# SCH_Geiger.net
KiCad netlist of a schematic drawn in EasyEDA
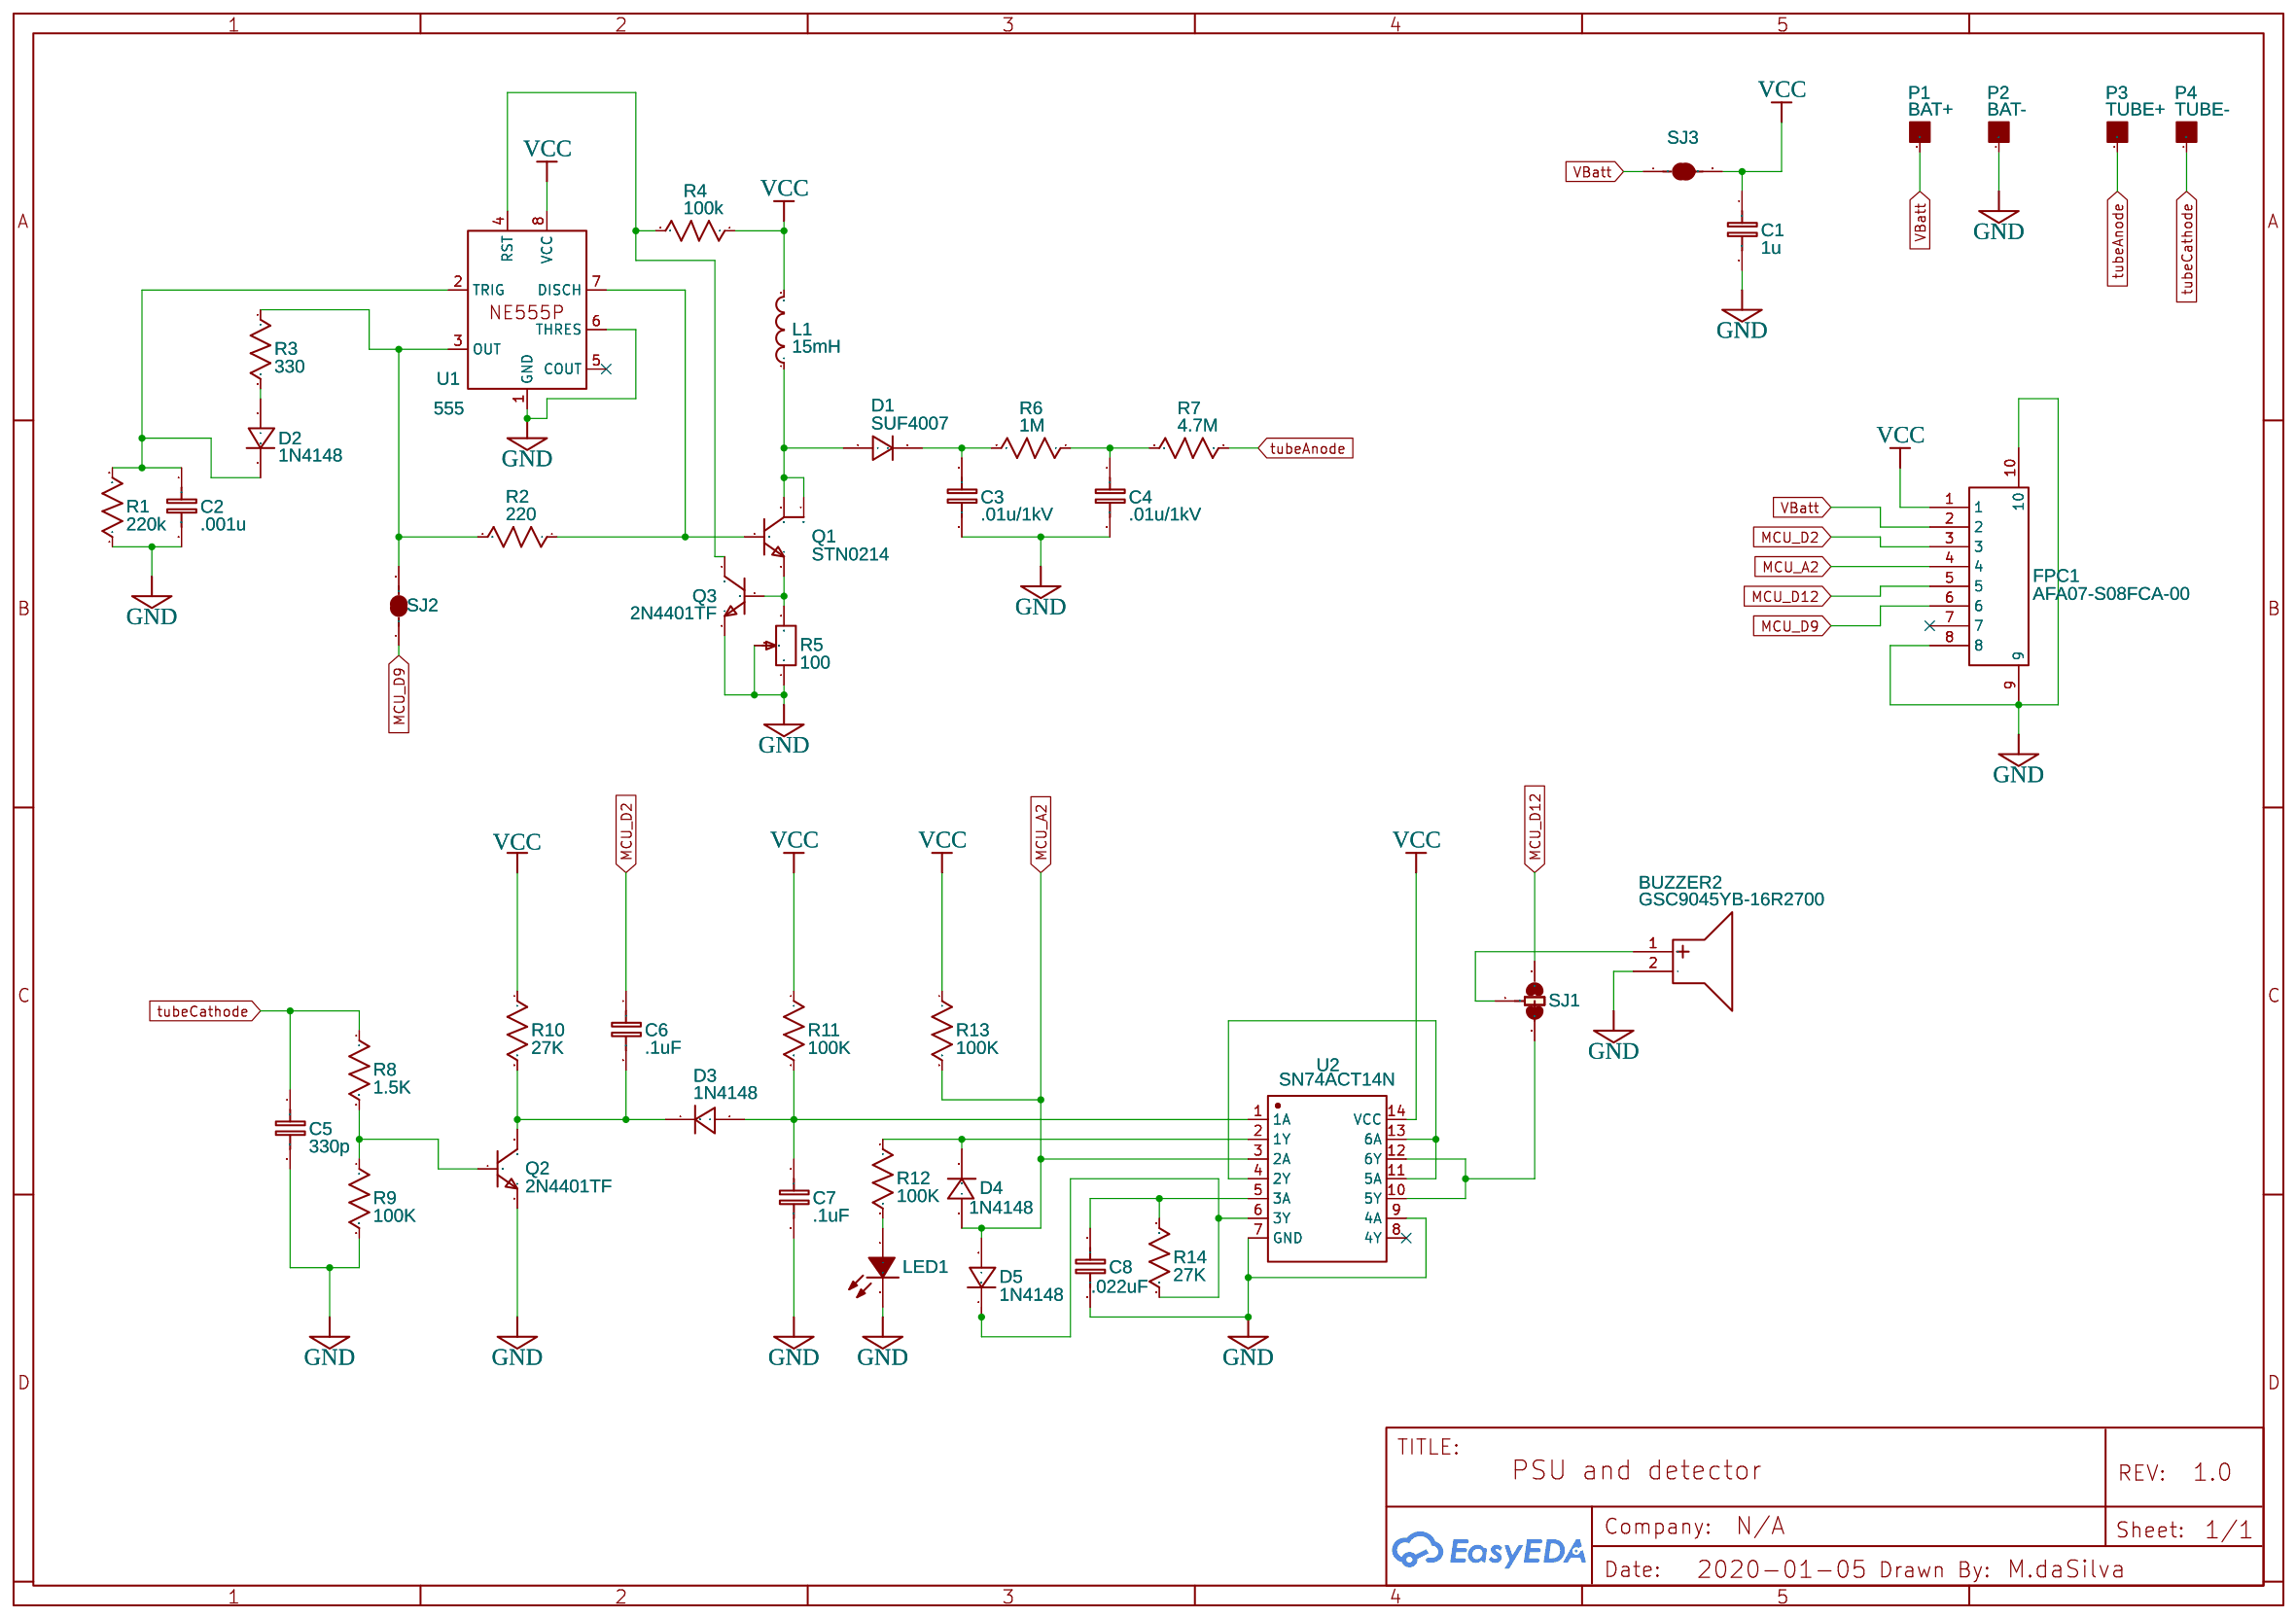
[diagram p0: schematic sheet]

(export (version "E")
  (design (tool "Eeschema 10.0.6"))
  (components
    (comp (ref "BUZZER2")
      (value "GSC9045YB-16R2700")
      (fields (field (name "BOM_Supplier Part") "C255324"))
      (libsource (lib "") (part "GSC9045YB-16R2700"))
    )
    (comp (ref "C1")
      (value "1u")
      (fields (field (name "BOM_Manufacturer Part") "0805B105K500AT"))
      (libsource (lib "") (part "Cap_RAD-0.1_EU_1"))
    )
    (comp (ref "C2")
      (value ".001u")
      (fields (field (name "BOM_Manufacturer Part") "0805B102J500NT"))
      (libsource (lib "") (part "Cap_RAD-0.1_EU_1"))
    )
    (comp (ref "C3")
      (value ".01u/1kV")
      (fields
        (field (name "BOM_Manufacturer Part") "1210B103K102NT")
        (field (name "BOM_Supplier Part") "C225089")
      )
      (libsource (lib "") (part "Cap_RAD-0.1_EU_2"))
    )
    (comp (ref "C4")
      (value ".01u/1kV")
      (fields
        (field (name "BOM_Manufacturer Part") "1210B103K102NT")
        (field (name "BOM_Supplier Part") "C225089")
      )
      (libsource (lib "") (part "Cap_RAD-0.1_EU_1"))
    )
    (comp (ref "C5")
      (value "330p")
      (fields (field (name "BOM_Manufacturer Part") "0805B331K101NT"))
      (libsource (lib "") (part "Cap_RAD-0.1_EU_3"))
    )
    (comp (ref "C6")
      (value ".1uF")
      (fields (field (name "BOM_Manufacturer Part") "0805B102J500NT"))
      (libsource (lib "") (part "Cap_RAD-0.1_EU"))
    )
    (comp (ref "C7")
      (value ".1uF")
      (fields (field (name "BOM_Manufacturer Part") "0805B104J500NT"))
      (libsource (lib "") (part "Cap_RAD-0.1_EU"))
    )
    (comp (ref "C8")
      (value ".022uF")
      (fields (field (name "BOM_Manufacturer Part") "CC0805KRX7R9BB223"))
      (libsource (lib "") (part "Cap_RAD-0.1_EU_3"))
    )
    (comp (ref "D1")
      (value "SUF4007")
      (fields (field (name "BOM_Supplier Part") "C212757"))
      (libsource (lib "") (part "SUF4007"))
    )
    (comp (ref "D2")
      (value "1N4148")
      (fields (field (name "BOM_Manufacturer Part") "1N4148W") (field (name "BOM_Supplier Part") "C402213"))
      (libsource (lib "") (part "1N4148W_C402213_1"))
    )
    (comp (ref "D3")
      (value "1N4148")
      (fields (field (name "BOM_Manufacturer Part") "1N4148W") (field (name "BOM_Supplier Part") "C402213"))
      (libsource (lib "") (part "1N4148W_C402213_2"))
    )
    (comp (ref "D4")
      (value "1N4148")
      (fields (field (name "BOM_Manufacturer Part") "1N4148W") (field (name "BOM_Supplier Part") "C402213"))
      (libsource (lib "") (part "1N4148W_C402213"))
    )
    (comp (ref "D5")
      (value "1N4148")
      (fields (field (name "BOM_Manufacturer Part") "1N4148W") (field (name "BOM_Supplier Part") "C402213"))
      (libsource (lib "") (part "1N4148W_C402213_1"))
    )
    (comp (ref "FPC1")
      (value "AFA07-S08FCA-00")
      (fields (field (name "BOM_Supplier Part") "C262714"))
      (libsource (lib "") (part "AFA07-S08FCA-00"))
    )
    (comp (ref "L1")
      (value "15mH")
      (fields
        (field (name "BOM_Manufacturer Part") "FNR6045S153KT")
        (field (name "BOM_Supplier Part") "C168110")
      )
      (libsource (lib "") (part "FNR6045S153KT"))
    )
    (comp (ref "LED1")
      (value "17-215/T7D-JU1V1E/3T")
      (fields (field (name "BOM_Supplier Part") "C264428"))
      (libsource (lib "") (part "17-215/T7D-JU1V1E/3T"))
    )
    (comp (ref "P1") (value "BAT+") (libsource (lib "") (part "3MMPAD")))
    (comp (ref "P2") (value "BAT-") (libsource (lib "") (part "3MMPAD")))
    (comp (ref "P3") (value "TUBE+") (libsource (lib "") (part "3MMPAD")))
    (comp (ref "P4") (value "TUBE-") (libsource (lib "") (part "3MMPAD")))
    (comp (ref "Q1") (value "STN0214") (libsource (lib "") (part "STN851")))
    (comp (ref "Q2")
      (value "2N4401TF")
      (fields (field (name "BOM_Supplier Part") "C83940"))
      (libsource (lib "") (part "2N4401TF"))
    )
    (comp (ref "Q3")
      (value "2N4401TF")
      (fields (field (name "BOM_Supplier Part") "C83940"))
      (libsource (lib "") (part "2N4401TF_1"))
    )
    (comp (ref "R1")
      (value "220k")
      (fields (field (name "BOM_Manufacturer Part") "RTT052203FTP"))
      (libsource (lib "") (part "Res_AXIAL-0.3(1/8W)_US_2"))
    )
    (comp (ref "R2")
      (value "220")
      (fields (field (name "BOM_Manufacturer Part") "RTT052200FTP"))
      (libsource (lib "") (part "Res_AXIAL-0.3(1/8W)_US_1"))
    )
    (comp (ref "R3")
      (value "330")
      (fields (field (name "BOM_Manufacturer Part") "RTT053300FTP"))
      (libsource (lib "") (part "Res_AXIAL-0.3(1/8W)_US"))
    )
    (comp (ref "R4")
      (value "100k")
      (fields (field (name "BOM_Manufacturer Part") "RTT051003FTP"))
      (libsource (lib "") (part "Res_AXIAL-0.3(1/8W)_US_1"))
    )
    (comp (ref "R5")
      (value "100")
      (fields
        (field (name "BOM_Manufacturer Part") "VG039NCHXTB101")
        (field (name "BOM_Supplier Part") "C128542")
      )
      (libsource (lib "") (part "VG039NCHXTB101"))
    )
    (comp (ref "R6")
      (value "1M")
      (fields (field (name "BOM_Manufacturer Part") "RTT051004FTP"))
      (libsource (lib "") (part "Res_AXIAL-0.3(1/8W)_US_1"))
    )
    (comp (ref "R7")
      (value "4.7M")
      (fields (field (name "BOM_Manufacturer Part") "RTT054704FTP"))
      (libsource (lib "") (part "Res_AXIAL-0.3(1/8W)_US_1"))
    )
    (comp (ref "R8")
      (value "1.5K")
      (fields (field (name "BOM_Manufacturer Part") "RTT051501FTP"))
      (libsource (lib "") (part "Res_AXIAL-0.3(1/8W)_US"))
    )
    (comp (ref "R9")
      (value "100K")
      (fields (field (name "BOM_Manufacturer Part") "RTT051003FTP"))
      (libsource (lib "") (part "Res_AXIAL-0.3(1/8W)_US"))
    )
    (comp (ref "R10")
      (value "27K")
      (fields (field (name "BOM_Manufacturer Part") "RTT052702FTP"))
      (libsource (lib "") (part "Res_AXIAL-0.3(1/8W)_US"))
    )
    (comp (ref "R11")
      (value "100K")
      (fields (field (name "BOM_Manufacturer Part") "RTT051003FTP"))
      (libsource (lib "") (part "Res_AXIAL-0.3(1/8W)_US"))
    )
    (comp (ref "R12")
      (value "100K")
      (fields (field (name "BOM_Manufacturer Part") "RTT051003FTP"))
      (libsource (lib "") (part "Res_AXIAL-0.3(1/8W)_US"))
    )
    (comp (ref "R13")
      (value "100K")
      (fields (field (name "BOM_Manufacturer Part") "RTT051003FTP"))
      (libsource (lib "") (part "Res_AXIAL-0.3(1/8W)_US"))
    )
    (comp (ref "R14")
      (value "27K")
      (fields (field (name "BOM_Manufacturer Part") "RTT052702FTP"))
      (libsource (lib "") (part "Res_AXIAL-0.3(1/8W)_US"))
    )
    (comp (ref "SJ1")
      (value "JUMPER-PAD-3-2OF3_NC_BY_TRACE_LARGE")
      (libsource (lib "") (part "JUMPER-PAD-3-2OF3_NC_BY_TRACE_LARGE"))
    )
    (comp (ref "SJ2") (value "JUMPER-PAD-2-NOYES_SILK") (libsource (lib "") (part "JUMPER-PAD-2-NOYES_SILK")))
    (comp (ref "SJ3")
      (value "JUMPER-PAD-2-NC_BY_TRACE")
      (libsource (lib "") (part "JUMPER-PAD-2-NC_BY_TRACE"))
    )
    (comp (ref "U1")
      (value "555")
      (fields (field (name "BOM_Manufacturer Part") "TLC555IDR") (field (name "BOM_Supplier Part") "C6987"))
      (libsource (lib "") (part "NE555P"))
    )
    (comp (ref "U2")
      (value "SN74ACT14N")
      (fields
        (field (name "BOM_Manufacturer Part") "MC74ACT14DR2G")
        (field (name "BOM_Supplier Part") "C7316")
      )
      (libsource (lib "") (part "SN74ACT14N"))
    )
  )
  (nets
    (net (code "1") (name "GND") (class "Default")
      (node (ref "BUZZER2") (pin "2") (pinfunction "-_2") (pintype "unspecified"))
      (node (ref "C1") (pin "2") (pinfunction "2_2") (pintype "unspecified"))
      (node (ref "C2") (pin "2") (pinfunction "2_2") (pintype "unspecified"))
      (node (ref "C3") (pin "2") (pinfunction "2_2") (pintype "unspecified"))
      (node (ref "C4") (pin "2") (pinfunction "2_2") (pintype "unspecified"))
      (node (ref "C5") (pin "2") (pinfunction "2_2") (pintype "unspecified"))
      (node (ref "C7") (pin "2") (pinfunction "2_2") (pintype "unspecified"))
      (node (ref "C8") (pin "2") (pinfunction "2_2") (pintype "unspecified"))
      (node (ref "FPC1") (pin "10") (pinfunction "10_10") (pintype "unspecified"))
      (node (ref "FPC1") (pin "8") (pinfunction "8_8") (pintype "unspecified"))
      (node (ref "FPC1") (pin "9") (pinfunction "9_9") (pintype "unspecified"))
      (node (ref "LED1") (pin "2") (pinfunction "K_2") (pintype "unspecified"))
      (node (ref "P2") (pin "1") (pinfunction "1_1") (pintype "unspecified"))
      (node (ref "Q2") (pin "2") (pinfunction "E_2") (pintype "unspecified"))
      (node (ref "Q3") (pin "2") (pinfunction "E_2") (pintype "unspecified"))
      (node (ref "R1") (pin "1") (pinfunction "1_1") (pintype "unspecified"))
      (node (ref "R5") (pin "1") (pinfunction "1_1") (pintype "input"))
      (node (ref "R5") (pin "2") (pinfunction "2_2") (pintype "input"))
      (node (ref "R9") (pin "2") (pinfunction "2_2") (pintype "unspecified"))
      (node (ref "U1") (pin "1") (pinfunction "GND_1") (pintype "unspecified"))
      (node (ref "U1") (pin "6") (pinfunction "THRES_6") (pintype "unspecified"))
      (node (ref "U2") (pin "7") (pinfunction "GND_7") (pintype "unspecified"))
      (node (ref "U2") (pin "9") (pinfunction "4A_9") (pintype "unspecified"))
    )
    (net (code "2") (name "MCU_A2") (class "Default")
      (node (ref "D4") (pin "2") (pinfunction "A_2") (pintype "unspecified"))
      (node (ref "D5") (pin "2") (pinfunction "A_2") (pintype "unspecified"))
      (node (ref "FPC1") (pin "4") (pinfunction "4_4") (pintype "unspecified"))
      (node (ref "R13") (pin "2") (pinfunction "2_2") (pintype "unspecified"))
      (node (ref "U2") (pin "3") (pinfunction "2A_3") (pintype "unspecified"))
    )
    (net (code "3") (name "MCU_D2") (class "Default")
      (node (ref "C6") (pin "1") (pinfunction "1_1") (pintype "unspecified"))
      (node (ref "FPC1") (pin "3") (pinfunction "3_3") (pintype "unspecified"))
    )
    (net (code "4") (name "MCU_D9") (class "Default")
      (node (ref "FPC1") (pin "6") (pinfunction "6_6") (pintype "unspecified"))
      (node (ref "SJ2") (pin "1") (pinfunction "1_1") (pintype "unspecified"))
    )
    (net (code "5") (name "MCU_D12") (class "Default")
      (node (ref "FPC1") (pin "5") (pinfunction "5_5") (pintype "unspecified"))
      (node (ref "SJ1") (pin "1") (pinfunction "1_1") (pintype "unspecified"))
    )
    (net (code "6") (name "Net-(BUZZER2-+)") (class "Default")
      (node (ref "BUZZER2") (pin "1") (pinfunction "+_1") (pintype "unspecified"))
      (node (ref "SJ1") (pin "2") (pinfunction "2_2") (pintype "unspecified"))
    )
    (net (code "7") (name "Net-(C4-Pad1)") (class "Default")
      (node (ref "C4") (pin "1") (pinfunction "1_1") (pintype "unspecified"))
      (node (ref "R6") (pin "1") (pinfunction "1_1") (pintype "unspecified"))
      (node (ref "R7") (pin "2") (pinfunction "2_2") (pintype "unspecified"))
    )
    (net (code "8") (name "Net-(D1-A)") (class "Default")
      (node (ref "C3") (pin "1") (pinfunction "1_1") (pintype "unspecified"))
      (node (ref "D1") (pin "1") (pinfunction "A_1") (pintype "unspecified"))
      (node (ref "R6") (pin "2") (pinfunction "2_2") (pintype "unspecified"))
    )
    (net (code "9") (name "Net-(D1-K)") (class "Default")
      (node (ref "D1") (pin "2") (pinfunction "K_2") (pintype "unspecified"))
      (node (ref "L1") (pin "1") (pinfunction "1_1") (pintype "unspecified"))
      (node (ref "Q1") (pin "2") (pinfunction "C_2") (pintype "unspecified"))
      (node (ref "Q1") (pin "4") (pinfunction "C_4") (pintype "unspecified"))
    )
    (net (code "10") (name "Net-(D2-A)") (class "Default")
      (node (ref "D2") (pin "2") (pinfunction "A_2") (pintype "unspecified"))
      (node (ref "R3") (pin "2") (pinfunction "2_2") (pintype "unspecified"))
    )
    (net (code "11") (name "Net-(D2-C)") (class "Default")
      (node (ref "C2") (pin "1") (pinfunction "1_1") (pintype "unspecified"))
      (node (ref "D2") (pin "1") (pinfunction "C_1") (pintype "unspecified"))
      (node (ref "R1") (pin "2") (pinfunction "2_2") (pintype "unspecified"))
      (node (ref "U1") (pin "2") (pinfunction "TRIG_2") (pintype "unspecified"))
    )
    (net (code "12") (name "Net-(D3-A)") (class "Default")
      (node (ref "C7") (pin "1") (pinfunction "1_1") (pintype "unspecified"))
      (node (ref "D3") (pin "2") (pinfunction "A_2") (pintype "unspecified"))
      (node (ref "R11") (pin "2") (pinfunction "2_2") (pintype "unspecified"))
      (node (ref "U2") (pin "1") (pinfunction "1A_1") (pintype "unspecified"))
    )
    (net (code "13") (name "Net-(D3-C)") (class "Default")
      (node (ref "C6") (pin "2") (pinfunction "2_2") (pintype "unspecified"))
      (node (ref "D3") (pin "1") (pinfunction "C_1") (pintype "unspecified"))
      (node (ref "Q2") (pin "3") (pinfunction "C_3") (pintype "unspecified"))
      (node (ref "R10") (pin "2") (pinfunction "2_2") (pintype "unspecified"))
    )
    (net (code "14") (name "Net-(D4-C)") (class "Default")
      (node (ref "D4") (pin "1") (pinfunction "C_1") (pintype "unspecified"))
      (node (ref "R12") (pin "1") (pinfunction "1_1") (pintype "unspecified"))
      (node (ref "U2") (pin "2") (pinfunction "1Y_2") (pintype "unspecified"))
    )
    (net (code "15") (name "Net-(D5-C)") (class "Default")
      (node (ref "D5") (pin "1") (pinfunction "C_1") (pintype "unspecified"))
      (node (ref "R14") (pin "2") (pinfunction "2_2") (pintype "unspecified"))
      (node (ref "U2") (pin "6") (pinfunction "3Y_6") (pintype "unspecified"))
    )
    (net (code "16") (name "Net-(LED1-A)") (class "Default")
      (node (ref "LED1") (pin "1") (pinfunction "A_1") (pintype "unspecified"))
      (node (ref "R12") (pin "2") (pinfunction "2_2") (pintype "unspecified"))
    )
    (net (code "17") (name "Net-(Q1-B)") (class "Default")
      (node (ref "Q1") (pin "1") (pinfunction "B_1") (pintype "unspecified"))
      (node (ref "R2") (pin "1") (pinfunction "1_1") (pintype "unspecified"))
      (node (ref "U1") (pin "7") (pinfunction "DISCH_7") (pintype "unspecified"))
    )
    (net (code "18") (name "Net-(Q1-E)") (class "Default")
      (node (ref "Q1") (pin "3") (pinfunction "E_3") (pintype "unspecified"))
      (node (ref "Q3") (pin "1") (pinfunction "B_1") (pintype "unspecified"))
      (node (ref "R5") (pin "3") (pinfunction "3_3") (pintype "input"))
    )
    (net (code "19") (name "Net-(Q2-B)") (class "Default")
      (node (ref "Q2") (pin "1") (pinfunction "B_1") (pintype "unspecified"))
      (node (ref "R8") (pin "2") (pinfunction "2_2") (pintype "unspecified"))
      (node (ref "R9") (pin "1") (pinfunction "1_1") (pintype "unspecified"))
    )
    (net (code "20") (name "Net-(Q3-C)") (class "Default")
      (node (ref "Q3") (pin "3") (pinfunction "C_3") (pintype "unspecified"))
      (node (ref "R4") (pin "2") (pinfunction "2_2") (pintype "unspecified"))
      (node (ref "U1") (pin "4") (pinfunction "RST_4") (pintype "unspecified"))
    )
    (net (code "21") (name "Net-(U1-OUT)") (class "Default")
      (node (ref "R2") (pin "2") (pinfunction "2_2") (pintype "unspecified"))
      (node (ref "R3") (pin "1") (pinfunction "1_1") (pintype "unspecified"))
      (node (ref "SJ2") (pin "2") (pinfunction "2_2") (pintype "unspecified"))
      (node (ref "U1") (pin "3") (pinfunction "OUT_3") (pintype "unspecified"))
    )
    (net (code "22") (name "Net-(U2-2Y)") (class "Default")
      (node (ref "U2") (pin "11") (pinfunction "5A_11") (pintype "unspecified"))
      (node (ref "U2") (pin "13") (pinfunction "6A_13") (pintype "unspecified"))
      (node (ref "U2") (pin "4") (pinfunction "2Y_4") (pintype "unspecified"))
    )
    (net (code "23") (name "Net-(U2-3A)") (class "Default")
      (node (ref "C8") (pin "1") (pinfunction "1_1") (pintype "unspecified"))
      (node (ref "R14") (pin "1") (pinfunction "1_1") (pintype "unspecified"))
      (node (ref "U2") (pin "5") (pinfunction "3A_5") (pintype "unspecified"))
    )
    (net (code "24") (name "Net-(U2-5Y)") (class "Default")
      (node (ref "SJ1") (pin "3") (pinfunction "3_3") (pintype "unspecified"))
      (node (ref "U2") (pin "10") (pinfunction "5Y_10") (pintype "unspecified"))
      (node (ref "U2") (pin "12") (pinfunction "6Y_12") (pintype "unspecified"))
    )
    (net (code "25") (name "VBatt") (class "Default")
      (node (ref "FPC1") (pin "2") (pinfunction "2_2") (pintype "unspecified"))
      (node (ref "P1") (pin "1") (pinfunction "1_1") (pintype "unspecified"))
      (node (ref "SJ3") (pin "1") (pinfunction "1_1") (pintype "unspecified"))
    )
    (net (code "26") (name "VCC") (class "Default")
      (node (ref "C1") (pin "1") (pinfunction "1_1") (pintype "unspecified"))
      (node (ref "FPC1") (pin "1") (pinfunction "1_1") (pintype "unspecified"))
      (node (ref "L1") (pin "2") (pinfunction "2_2") (pintype "unspecified"))
      (node (ref "R10") (pin "1") (pinfunction "1_1") (pintype "unspecified"))
      (node (ref "R11") (pin "1") (pinfunction "1_1") (pintype "unspecified"))
      (node (ref "R13") (pin "1") (pinfunction "1_1") (pintype "unspecified"))
      (node (ref "R4") (pin "1") (pinfunction "1_1") (pintype "unspecified"))
      (node (ref "SJ3") (pin "2") (pinfunction "2_2") (pintype "unspecified"))
      (node (ref "U1") (pin "8") (pinfunction "VCC_8") (pintype "unspecified"))
      (node (ref "U2") (pin "14") (pinfunction "VCC_14") (pintype "unspecified"))
    )
    (net (code "27") (name "tubeAnode") (class "Default")
      (node (ref "P3") (pin "1") (pinfunction "1_1") (pintype "unspecified"))
      (node (ref "R7") (pin "1") (pinfunction "1_1") (pintype "unspecified"))
    )
    (net (code "28") (name "tubeCathode") (class "Default")
      (node (ref "C5") (pin "1") (pinfunction "1_1") (pintype "unspecified"))
      (node (ref "P4") (pin "1") (pinfunction "1_1") (pintype "unspecified"))
      (node (ref "R8") (pin "1") (pinfunction "1_1") (pintype "unspecified"))
    )
    (net (code "29") (name "unconnected-(FPC1-Pad7)") (class "Default")
      (node (ref "FPC1") (pin "7") (pinfunction "7_7") (pintype "unspecified+no_connect"))
    )
    (net (code "30") (name "unconnected-(U1-COUT-Pad5)") (class "Default")
      (node (ref "U1") (pin "5") (pinfunction "COUT_5") (pintype "unspecified+no_connect"))
    )
    (net (code "31") (name "unconnected-(U2-4Y-Pad8)") (class "Default")
      (node (ref "U2") (pin "8") (pinfunction "4Y_8") (pintype "unspecified+no_connect"))
    )
  )
)
